# v1_1.net
KiCad netlist of a schematic drawn in Altium Designer
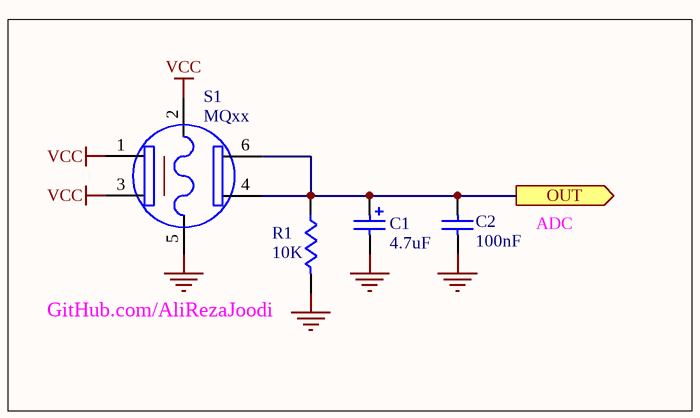
[diagram p0: v1.1.SchDoc]

(export (version "E")
  (design (tool "Eeschema 10.0.6"))
  (components
    (comp (ref "C1")
      (value "4.7uF")
      (footprint "CAPPR2.5-6.3x5")
      (description "Polarized Capacitor (Radial)")
      (fields
        (field (name "MANUFACTURER") "Generic Components")
        (field (name "Comment") "Cap Pol1")
        (field (name "PUBLISHER") "Altium Limited")
      )
      (libsource (lib "Miscellaneous Devices") (part "Cap Pol1"))
    )
    (comp (ref "C2")
      (value "100nF")
      (footprint "C_THD_CER_(P2.54-D3.5-T1.5)")
      (description "Capacitor, Ceramic Multilayer")
      (libsource (lib "Passive") (part "Capacitor_Ceramic"))
    )
    (comp (ref "R1")
      (value "10K")
      (footprint "AXIAL-0.4")
      (description "Resistor")
      (fields
        (field (name "MANUFACTURER") "Generic Components")
        (field (name "Comment") "Res1")
        (field (name "PUBLISHER") "Altium Limited")
      )
      (libsource (lib "Miscellaneous Devices") (part "Res1"))
    )
    (comp (ref "S1")
      (value "MQxx")
      (footprint "MQxx")
      (description "Gas Sensor")
      (fields (field (name "MANUFACTURER") "Generic Components") (field (name "PUBLISHER") "Altium Limited"))
      (libsource (lib "Miscellaneous Devices") (part "MQ"))
    )
  )
  (nets
    (net (code "1") (name "/OUT") (class "Default")
      (node (ref "C1") (pin "1") (pinfunction "1_1") (pintype "passive"))
      (node (ref "C2") (pin "1") (pinfunction "1_1") (pintype "passive"))
      (node (ref "R1") (pin "1") (pinfunction "1_1") (pintype "passive"))
      (node (ref "S1") (pin "4") (pinfunction "33_4") (pintype "passive"))
      (node (ref "S1") (pin "6") (pinfunction "6_6") (pintype "passive"))
    )
    (net (code "2") (name "GND") (class "Default")
      (node (ref "C1") (pin "2") (pinfunction "2_2") (pintype "passive"))
      (node (ref "C2") (pin "2") (pinfunction "2_2") (pintype "passive"))
      (node (ref "R1") (pin "2") (pinfunction "2_2") (pintype "passive"))
      (node (ref "S1") (pin "5") (pinfunction "5_5") (pintype "passive"))
    )
    (net (code "3") (name "VCC") (class "Default")
      (node (ref "S1") (pin "1") (pinfunction "31_1") (pintype "passive"))
      (node (ref "S1") (pin "2") (pinfunction "2_2") (pintype "passive"))
      (node (ref "S1") (pin "3") (pinfunction "3_3") (pintype "passive"))
    )
  )
)
